# LMS7002M_Power.net
KiCad netlist of a schematic drawn in Altium Designer
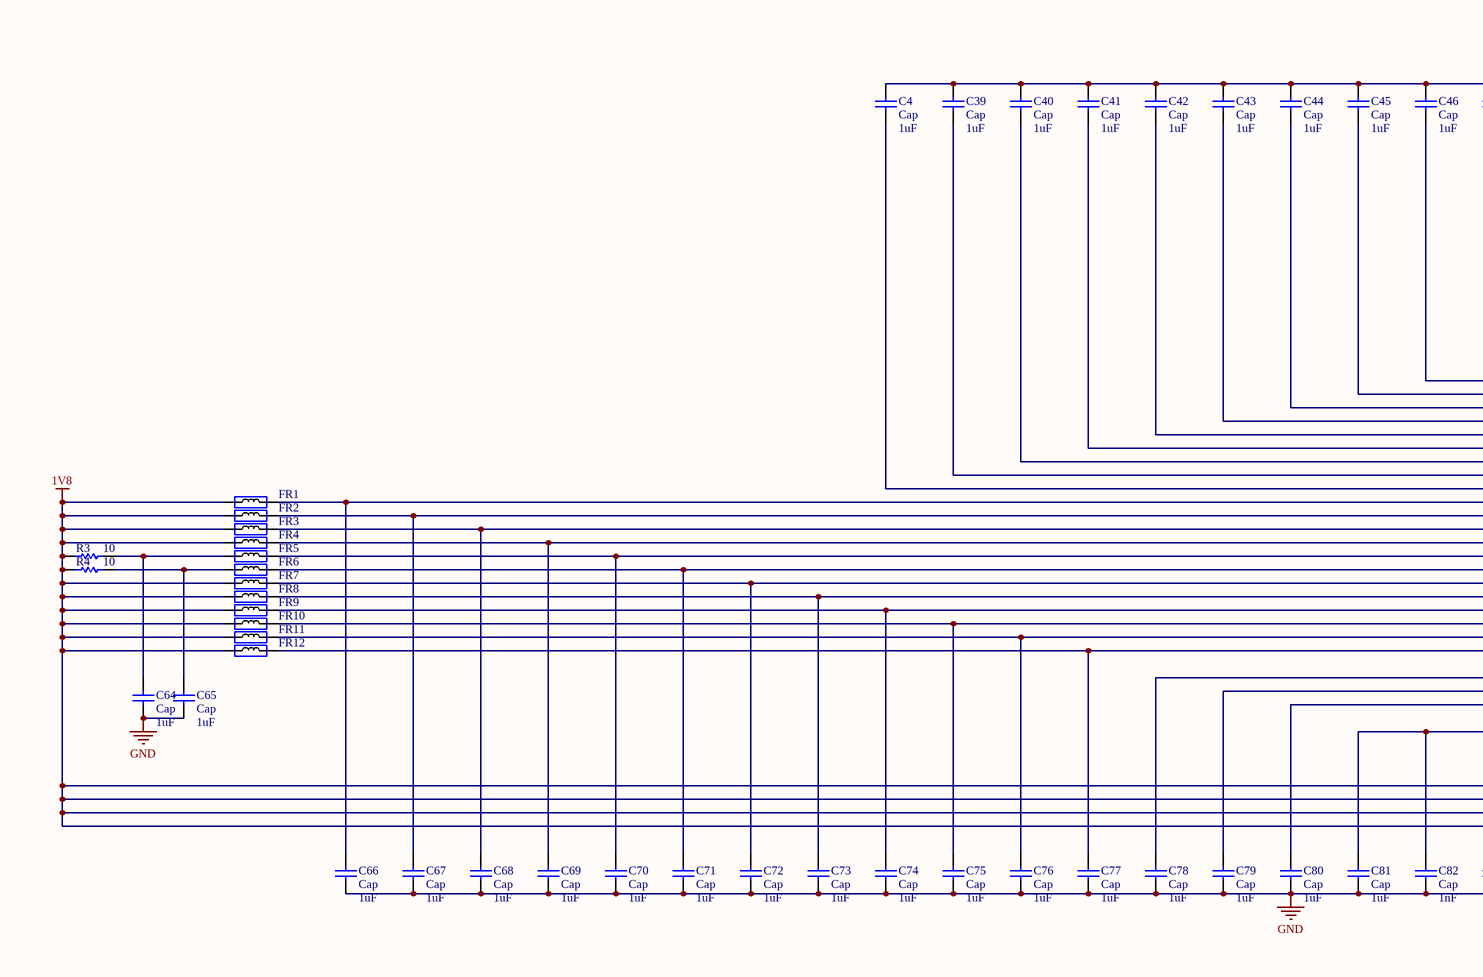
[diagram p0: LMS7002M Power.SchDoc, left]
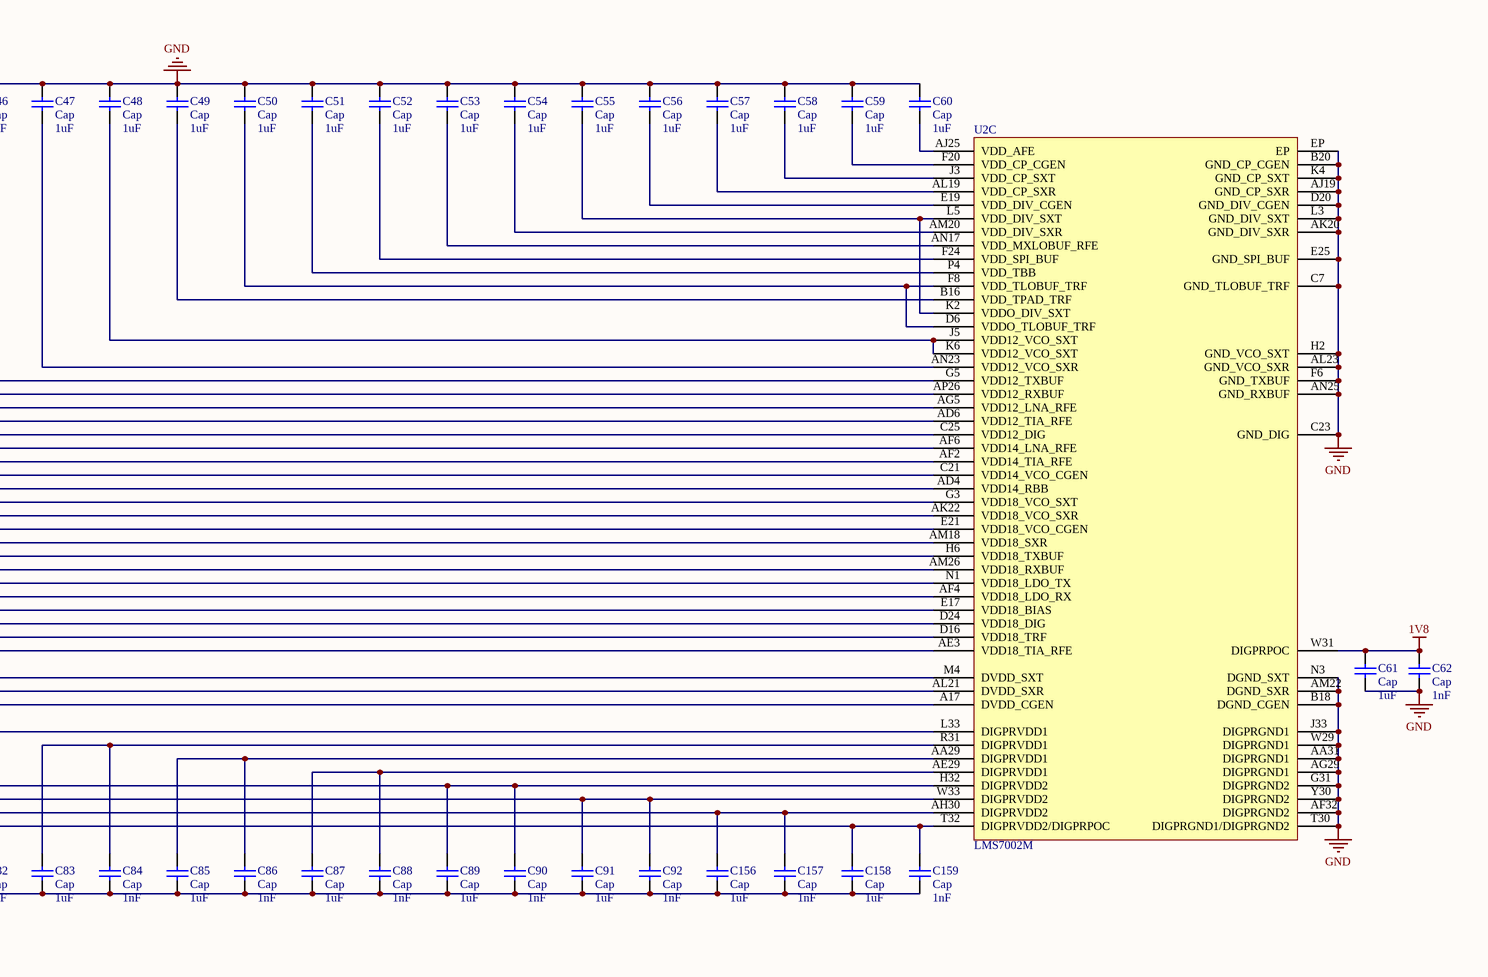
[diagram p1: LMS7002M Power.SchDoc, right]

(export (version "E")
  (design (tool "Eeschema 10.0.6"))
  (components
    (comp (ref "C4")
      (value "Cap")
      (footprint "0603")
      (description "Capacitor")
      (fields (field (name "ALTIUM_VALUE") "1uF") (field (name "PUBLISHER") "Altium Limited"))
      (libsource (lib "Miscellaneous Devices") (part "Cap"))
    )
    (comp (ref "C39")
      (value "Cap")
      (footprint "0603")
      (description "Capacitor")
      (fields (field (name "ALTIUM_VALUE") "1uF") (field (name "PUBLISHER") "Altium Limited"))
      (libsource (lib "Miscellaneous Devices") (part "Cap"))
    )
    (comp (ref "C40")
      (value "Cap")
      (footprint "0603")
      (description "Capacitor")
      (fields (field (name "ALTIUM_VALUE") "1uF") (field (name "PUBLISHER") "Altium Limited"))
      (libsource (lib "Miscellaneous Devices") (part "Cap"))
    )
    (comp (ref "C41")
      (value "Cap")
      (footprint "0603")
      (description "Capacitor")
      (fields (field (name "ALTIUM_VALUE") "1uF") (field (name "PUBLISHER") "Altium Limited"))
      (libsource (lib "Miscellaneous Devices") (part "Cap"))
    )
    (comp (ref "C42")
      (value "Cap")
      (footprint "0603")
      (description "Capacitor")
      (fields (field (name "ALTIUM_VALUE") "1uF") (field (name "PUBLISHER") "Altium Limited"))
      (libsource (lib "Miscellaneous Devices") (part "Cap"))
    )
    (comp (ref "C43")
      (value "Cap")
      (footprint "0603")
      (description "Capacitor")
      (fields (field (name "ALTIUM_VALUE") "1uF") (field (name "PUBLISHER") "Altium Limited"))
      (libsource (lib "Miscellaneous Devices") (part "Cap"))
    )
    (comp (ref "C44")
      (value "Cap")
      (footprint "0603")
      (description "Capacitor")
      (fields (field (name "ALTIUM_VALUE") "1uF") (field (name "PUBLISHER") "Altium Limited"))
      (libsource (lib "Miscellaneous Devices") (part "Cap"))
    )
    (comp (ref "C45")
      (value "Cap")
      (footprint "0603")
      (description "Capacitor")
      (fields (field (name "ALTIUM_VALUE") "1uF") (field (name "PUBLISHER") "Altium Limited"))
      (libsource (lib "Miscellaneous Devices") (part "Cap"))
    )
    (comp (ref "C46")
      (value "Cap")
      (footprint "0603")
      (description "Capacitor")
      (fields (field (name "ALTIUM_VALUE") "1uF") (field (name "PUBLISHER") "Altium Limited"))
      (libsource (lib "Miscellaneous Devices") (part "Cap"))
    )
    (comp (ref "C47")
      (value "Cap")
      (footprint "0603")
      (description "Capacitor")
      (fields (field (name "ALTIUM_VALUE") "1uF") (field (name "PUBLISHER") "Altium Limited"))
      (libsource (lib "Miscellaneous Devices") (part "Cap"))
    )
    (comp (ref "C48")
      (value "Cap")
      (footprint "0603")
      (description "Capacitor")
      (fields (field (name "ALTIUM_VALUE") "1uF") (field (name "PUBLISHER") "Altium Limited"))
      (libsource (lib "Miscellaneous Devices") (part "Cap"))
    )
    (comp (ref "C49")
      (value "Cap")
      (footprint "0603")
      (description "Capacitor")
      (fields (field (name "ALTIUM_VALUE") "1uF") (field (name "PUBLISHER") "Altium Limited"))
      (libsource (lib "Miscellaneous Devices") (part "Cap"))
    )
    (comp (ref "C50")
      (value "Cap")
      (footprint "0603")
      (description "Capacitor")
      (fields (field (name "ALTIUM_VALUE") "1uF") (field (name "PUBLISHER") "Altium Limited"))
      (libsource (lib "Miscellaneous Devices") (part "Cap"))
    )
    (comp (ref "C51")
      (value "Cap")
      (footprint "0603")
      (description "Capacitor")
      (fields (field (name "ALTIUM_VALUE") "1uF") (field (name "PUBLISHER") "Altium Limited"))
      (libsource (lib "Miscellaneous Devices") (part "Cap"))
    )
    (comp (ref "C52")
      (value "Cap")
      (footprint "0603")
      (description "Capacitor")
      (fields (field (name "ALTIUM_VALUE") "1uF") (field (name "PUBLISHER") "Altium Limited"))
      (libsource (lib "Miscellaneous Devices") (part "Cap"))
    )
    (comp (ref "C53")
      (value "Cap")
      (footprint "0603")
      (description "Capacitor")
      (fields (field (name "ALTIUM_VALUE") "1uF") (field (name "PUBLISHER") "Altium Limited"))
      (libsource (lib "Miscellaneous Devices") (part "Cap"))
    )
    (comp (ref "C54")
      (value "Cap")
      (footprint "0603")
      (description "Capacitor")
      (fields (field (name "ALTIUM_VALUE") "1uF") (field (name "PUBLISHER") "Altium Limited"))
      (libsource (lib "Miscellaneous Devices") (part "Cap"))
    )
    (comp (ref "C55")
      (value "Cap")
      (footprint "0603")
      (description "Capacitor")
      (fields (field (name "ALTIUM_VALUE") "1uF") (field (name "PUBLISHER") "Altium Limited"))
      (libsource (lib "Miscellaneous Devices") (part "Cap"))
    )
    (comp (ref "C56")
      (value "Cap")
      (footprint "0603")
      (description "Capacitor")
      (fields (field (name "ALTIUM_VALUE") "1uF") (field (name "PUBLISHER") "Altium Limited"))
      (libsource (lib "Miscellaneous Devices") (part "Cap"))
    )
    (comp (ref "C57")
      (value "Cap")
      (footprint "0603")
      (description "Capacitor")
      (fields (field (name "ALTIUM_VALUE") "1uF") (field (name "PUBLISHER") "Altium Limited"))
      (libsource (lib "Miscellaneous Devices") (part "Cap"))
    )
    (comp (ref "C58")
      (value "Cap")
      (footprint "0603")
      (description "Capacitor")
      (fields (field (name "ALTIUM_VALUE") "1uF") (field (name "PUBLISHER") "Altium Limited"))
      (libsource (lib "Miscellaneous Devices") (part "Cap"))
    )
    (comp (ref "C59")
      (value "Cap")
      (footprint "0603")
      (description "Capacitor")
      (fields (field (name "ALTIUM_VALUE") "1uF") (field (name "PUBLISHER") "Altium Limited"))
      (libsource (lib "Miscellaneous Devices") (part "Cap"))
    )
    (comp (ref "C60")
      (value "Cap")
      (footprint "0603")
      (description "Capacitor")
      (fields (field (name "ALTIUM_VALUE") "1uF") (field (name "PUBLISHER") "Altium Limited"))
      (libsource (lib "Miscellaneous Devices") (part "Cap"))
    )
    (comp (ref "C61")
      (value "Cap")
      (footprint "0603")
      (description "Capacitor")
      (fields (field (name "ALTIUM_VALUE") "1uF") (field (name "PUBLISHER") "Altium Limited"))
      (libsource (lib "Miscellaneous Devices") (part "Cap"))
    )
    (comp (ref "C62")
      (value "Cap")
      (footprint "0603")
      (description "Capacitor")
      (fields (field (name "ALTIUM_VALUE") "1nF") (field (name "PUBLISHER") "Altium Limited"))
      (libsource (lib "Miscellaneous Devices") (part "Cap"))
    )
    (comp (ref "C64")
      (value "Cap")
      (footprint "0603")
      (description "Capacitor")
      (fields (field (name "ALTIUM_VALUE") "1uF") (field (name "PUBLISHER") "Altium Limited"))
      (libsource (lib "Miscellaneous Devices") (part "Cap"))
    )
    (comp (ref "C65")
      (value "Cap")
      (footprint "0603")
      (description "Capacitor")
      (fields (field (name "ALTIUM_VALUE") "1uF") (field (name "PUBLISHER") "Altium Limited"))
      (libsource (lib "Miscellaneous Devices") (part "Cap"))
    )
    (comp (ref "C66")
      (value "Cap")
      (footprint "0603")
      (description "Capacitor")
      (fields (field (name "ALTIUM_VALUE") "1uF") (field (name "PUBLISHER") "Altium Limited"))
      (libsource (lib "Miscellaneous Devices") (part "Cap"))
    )
    (comp (ref "C67")
      (value "Cap")
      (footprint "0603")
      (description "Capacitor")
      (fields (field (name "ALTIUM_VALUE") "1uF") (field (name "PUBLISHER") "Altium Limited"))
      (libsource (lib "Miscellaneous Devices") (part "Cap"))
    )
    (comp (ref "C68")
      (value "Cap")
      (footprint "0603")
      (description "Capacitor")
      (fields (field (name "ALTIUM_VALUE") "1uF") (field (name "PUBLISHER") "Altium Limited"))
      (libsource (lib "Miscellaneous Devices") (part "Cap"))
    )
    (comp (ref "C69")
      (value "Cap")
      (footprint "0603")
      (description "Capacitor")
      (fields (field (name "ALTIUM_VALUE") "1uF") (field (name "PUBLISHER") "Altium Limited"))
      (libsource (lib "Miscellaneous Devices") (part "Cap"))
    )
    (comp (ref "C70")
      (value "Cap")
      (footprint "0603")
      (description "Capacitor")
      (fields (field (name "ALTIUM_VALUE") "1uF") (field (name "PUBLISHER") "Altium Limited"))
      (libsource (lib "Miscellaneous Devices") (part "Cap"))
    )
    (comp (ref "C71")
      (value "Cap")
      (footprint "0603")
      (description "Capacitor")
      (fields (field (name "ALTIUM_VALUE") "1uF") (field (name "PUBLISHER") "Altium Limited"))
      (libsource (lib "Miscellaneous Devices") (part "Cap"))
    )
    (comp (ref "C72")
      (value "Cap")
      (footprint "0603")
      (description "Capacitor")
      (fields (field (name "ALTIUM_VALUE") "1uF") (field (name "PUBLISHER") "Altium Limited"))
      (libsource (lib "Miscellaneous Devices") (part "Cap"))
    )
    (comp (ref "C73")
      (value "Cap")
      (footprint "0603")
      (description "Capacitor")
      (fields (field (name "ALTIUM_VALUE") "1uF") (field (name "PUBLISHER") "Altium Limited"))
      (libsource (lib "Miscellaneous Devices") (part "Cap"))
    )
    (comp (ref "C74")
      (value "Cap")
      (footprint "0603")
      (description "Capacitor")
      (fields (field (name "ALTIUM_VALUE") "1uF") (field (name "PUBLISHER") "Altium Limited"))
      (libsource (lib "Miscellaneous Devices") (part "Cap"))
    )
    (comp (ref "C75")
      (value "Cap")
      (footprint "0603")
      (description "Capacitor")
      (fields (field (name "ALTIUM_VALUE") "1uF") (field (name "PUBLISHER") "Altium Limited"))
      (libsource (lib "Miscellaneous Devices") (part "Cap"))
    )
    (comp (ref "C76")
      (value "Cap")
      (footprint "0603")
      (description "Capacitor")
      (fields (field (name "ALTIUM_VALUE") "1uF") (field (name "PUBLISHER") "Altium Limited"))
      (libsource (lib "Miscellaneous Devices") (part "Cap"))
    )
    (comp (ref "C77")
      (value "Cap")
      (footprint "0603")
      (description "Capacitor")
      (fields (field (name "ALTIUM_VALUE") "1uF") (field (name "PUBLISHER") "Altium Limited"))
      (libsource (lib "Miscellaneous Devices") (part "Cap"))
    )
    (comp (ref "C78")
      (value "Cap")
      (footprint "0603")
      (description "Capacitor")
      (fields (field (name "ALTIUM_VALUE") "1uF") (field (name "PUBLISHER") "Altium Limited"))
      (libsource (lib "Miscellaneous Devices") (part "Cap"))
    )
    (comp (ref "C79")
      (value "Cap")
      (footprint "0603")
      (description "Capacitor")
      (fields (field (name "ALTIUM_VALUE") "1uF") (field (name "PUBLISHER") "Altium Limited"))
      (libsource (lib "Miscellaneous Devices") (part "Cap"))
    )
    (comp (ref "C80")
      (value "Cap")
      (footprint "0603")
      (description "Capacitor")
      (fields (field (name "ALTIUM_VALUE") "1uF") (field (name "PUBLISHER") "Altium Limited"))
      (libsource (lib "Miscellaneous Devices") (part "Cap"))
    )
    (comp (ref "C81")
      (value "Cap")
      (footprint "0603")
      (description "Capacitor")
      (fields (field (name "ALTIUM_VALUE") "1uF") (field (name "PUBLISHER") "Altium Limited"))
      (libsource (lib "Miscellaneous Devices") (part "Cap"))
    )
    (comp (ref "C82")
      (value "Cap")
      (footprint "0603")
      (description "Capacitor")
      (fields (field (name "ALTIUM_VALUE") "1nF") (field (name "PUBLISHER") "Altium Limited"))
      (libsource (lib "Miscellaneous Devices") (part "Cap"))
    )
    (comp (ref "C83")
      (value "Cap")
      (footprint "0603")
      (description "Capacitor")
      (fields (field (name "ALTIUM_VALUE") "1uF") (field (name "PUBLISHER") "Altium Limited"))
      (libsource (lib "Miscellaneous Devices") (part "Cap"))
    )
    (comp (ref "C84")
      (value "Cap")
      (footprint "0603")
      (description "Capacitor")
      (fields (field (name "ALTIUM_VALUE") "1nF") (field (name "PUBLISHER") "Altium Limited"))
      (libsource (lib "Miscellaneous Devices") (part "Cap"))
    )
    (comp (ref "C85")
      (value "Cap")
      (footprint "0603")
      (description "Capacitor")
      (fields (field (name "ALTIUM_VALUE") "1uF") (field (name "PUBLISHER") "Altium Limited"))
      (libsource (lib "Miscellaneous Devices") (part "Cap"))
    )
    (comp (ref "C86")
      (value "Cap")
      (footprint "0603")
      (description "Capacitor")
      (fields (field (name "ALTIUM_VALUE") "1nF") (field (name "PUBLISHER") "Altium Limited"))
      (libsource (lib "Miscellaneous Devices") (part "Cap"))
    )
    (comp (ref "C87")
      (value "Cap")
      (footprint "0603")
      (description "Capacitor")
      (fields (field (name "ALTIUM_VALUE") "1uF") (field (name "PUBLISHER") "Altium Limited"))
      (libsource (lib "Miscellaneous Devices") (part "Cap"))
    )
    (comp (ref "C88")
      (value "Cap")
      (footprint "0603")
      (description "Capacitor")
      (fields (field (name "ALTIUM_VALUE") "1nF") (field (name "PUBLISHER") "Altium Limited"))
      (libsource (lib "Miscellaneous Devices") (part "Cap"))
    )
    (comp (ref "C89")
      (value "Cap")
      (footprint "0603")
      (description "Capacitor")
      (fields (field (name "ALTIUM_VALUE") "1uF") (field (name "PUBLISHER") "Altium Limited"))
      (libsource (lib "Miscellaneous Devices") (part "Cap"))
    )
    (comp (ref "C90")
      (value "Cap")
      (footprint "0603")
      (description "Capacitor")
      (fields (field (name "ALTIUM_VALUE") "1nF") (field (name "PUBLISHER") "Altium Limited"))
      (libsource (lib "Miscellaneous Devices") (part "Cap"))
    )
    (comp (ref "C91")
      (value "Cap")
      (footprint "0603")
      (description "Capacitor")
      (fields (field (name "ALTIUM_VALUE") "1uF") (field (name "PUBLISHER") "Altium Limited"))
      (libsource (lib "Miscellaneous Devices") (part "Cap"))
    )
    (comp (ref "C92")
      (value "Cap")
      (footprint "0603")
      (description "Capacitor")
      (fields (field (name "ALTIUM_VALUE") "1nF") (field (name "PUBLISHER") "Altium Limited"))
      (libsource (lib "Miscellaneous Devices") (part "Cap"))
    )
    (comp (ref "C156")
      (value "Cap")
      (footprint "0603")
      (description "Capacitor")
      (fields (field (name "ALTIUM_VALUE") "1uF") (field (name "PUBLISHER") "Altium Limited"))
      (libsource (lib "Miscellaneous Devices") (part "Cap"))
    )
    (comp (ref "C157")
      (value "Cap")
      (footprint "0603")
      (description "Capacitor")
      (fields (field (name "ALTIUM_VALUE") "1nF") (field (name "PUBLISHER") "Altium Limited"))
      (libsource (lib "Miscellaneous Devices") (part "Cap"))
    )
    (comp (ref "C158")
      (value "Cap")
      (footprint "0603")
      (description "Capacitor")
      (fields (field (name "ALTIUM_VALUE") "1uF") (field (name "PUBLISHER") "Altium Limited"))
      (libsource (lib "Miscellaneous Devices") (part "Cap"))
    )
    (comp (ref "C159")
      (value "Cap")
      (footprint "0603")
      (description "Capacitor")
      (fields (field (name "ALTIUM_VALUE") "1nF") (field (name "PUBLISHER") "Altium Limited"))
      (libsource (lib "Miscellaneous Devices") (part "Cap"))
    )
    (comp (ref "FR1")
      (value "600R, 0.27A")
      (footprint "0603")
      (fields (field (name "MANUFACTURER") "Taiyo Yuden"))
      (libsource (lib "LimeMicroAltiumLib_schLib") (part "Ferrite"))
    )
    (comp (ref "FR2")
      (value "600R, 0.27A")
      (footprint "0603")
      (fields (field (name "MANUFACTURER") "Taiyo Yuden"))
      (libsource (lib "LimeMicroAltiumLib_schLib") (part "Ferrite"))
    )
    (comp (ref "FR3")
      (value "600R, 0.27A")
      (footprint "0603")
      (fields (field (name "MANUFACTURER") "Taiyo Yuden"))
      (libsource (lib "LimeMicroAltiumLib_schLib") (part "Ferrite"))
    )
    (comp (ref "FR4")
      (value "600R, 0.27A")
      (footprint "0603")
      (fields (field (name "MANUFACTURER") "Taiyo Yuden"))
      (libsource (lib "LimeMicroAltiumLib_schLib") (part "Ferrite"))
    )
    (comp (ref "FR5")
      (value "600R, 0.27A")
      (footprint "0603")
      (fields (field (name "MANUFACTURER") "Taiyo Yuden"))
      (libsource (lib "LimeMicroAltiumLib_schLib") (part "Ferrite"))
    )
    (comp (ref "FR6")
      (value "600R, 0.27A")
      (footprint "0603")
      (fields (field (name "MANUFACTURER") "Taiyo Yuden"))
      (libsource (lib "LimeMicroAltiumLib_schLib") (part "Ferrite"))
    )
    (comp (ref "FR7")
      (value "600R, 0.27A")
      (footprint "0603")
      (fields (field (name "MANUFACTURER") "Taiyo Yuden"))
      (libsource (lib "LimeMicroAltiumLib_schLib") (part "Ferrite"))
    )
    (comp (ref "FR8")
      (value "600R, 0.27A")
      (footprint "0603")
      (fields (field (name "MANUFACTURER") "Taiyo Yuden"))
      (libsource (lib "LimeMicroAltiumLib_schLib") (part "Ferrite"))
    )
    (comp (ref "FR9")
      (value "600R, 0.27A")
      (footprint "0603")
      (fields (field (name "MANUFACTURER") "Taiyo Yuden"))
      (libsource (lib "LimeMicroAltiumLib_schLib") (part "Ferrite"))
    )
    (comp (ref "FR10")
      (value "600R, 0.27A")
      (footprint "0603")
      (fields (field (name "MANUFACTURER") "Taiyo Yuden"))
      (libsource (lib "LimeMicroAltiumLib_schLib") (part "Ferrite"))
    )
    (comp (ref "FR11")
      (value "600R, 0.27A")
      (footprint "0603")
      (fields (field (name "MANUFACTURER") "Taiyo Yuden"))
      (libsource (lib "LimeMicroAltiumLib_schLib") (part "Ferrite"))
    )
    (comp (ref "FR12")
      (value "600R, 0.27A")
      (footprint "0603")
      (fields (field (name "MANUFACTURER") "Taiyo Yuden"))
      (libsource (lib "LimeMicroAltiumLib_schLib") (part "Ferrite"))
    )
    (comp (ref "R3")
      (value "10")
      (footprint "0402-A")
      (description "Resistor")
      (fields (field (name "Comment") "Res1") (field (name "PUBLISHER") "Altium Limited"))
      (libsource (lib "Miscellaneous Devices") (part "Res1"))
    )
    (comp (ref "R4")
      (value "10")
      (footprint "0402-A")
      (description "Resistor")
      (fields (field (name "Comment") "Res1") (field (name "PUBLISHER") "Altium Limited"))
      (libsource (lib "Miscellaneous Devices") (part "Res1"))
    )
    (comp (ref "U2")
      (value "LMS7002M")
      (footprint "LM-QFN-261_V")
      (fields (field (name "MANUFACTURER") "LimeMicrosystemsLtd"))
      (libsource (lib "Altium Content Vault") (part "LM-LMS7002M-QFN-261"))
    )
  )
  (nets
    (net (code "1") (name "1V8") (class "Default")
      (node (ref "C156") (pin "2") (pinfunction "2_2") (pintype "passive"))
      (node (ref "C157") (pin "2") (pinfunction "2_2") (pintype "passive"))
      (node (ref "C158") (pin "2") (pinfunction "2_2") (pintype "passive"))
      (node (ref "C159") (pin "2") (pinfunction "2_2") (pintype "passive"))
      (node (ref "C61") (pin "2") (pinfunction "2_2") (pintype "passive"))
      (node (ref "C62") (pin "2") (pinfunction "2_2") (pintype "passive"))
      (node (ref "C89") (pin "2") (pinfunction "2_2") (pintype "passive"))
      (node (ref "C90") (pin "2") (pinfunction "2_2") (pintype "passive"))
      (node (ref "C91") (pin "2") (pinfunction "2_2") (pintype "passive"))
      (node (ref "C92") (pin "2") (pinfunction "2_2") (pintype "passive"))
      (node (ref "FR1") (pin "1") (pinfunction "1_1") (pintype "passive"))
      (node (ref "FR10") (pin "1") (pinfunction "1_1") (pintype "passive"))
      (node (ref "FR11") (pin "1") (pinfunction "1_1") (pintype "passive"))
      (node (ref "FR12") (pin "1") (pinfunction "1_1") (pintype "passive"))
      (node (ref "FR2") (pin "1") (pinfunction "1_1") (pintype "passive"))
      (node (ref "FR3") (pin "1") (pinfunction "1_1") (pintype "passive"))
      (node (ref "FR4") (pin "1") (pinfunction "1_1") (pintype "passive"))
      (node (ref "FR7") (pin "1") (pinfunction "1_1") (pintype "passive"))
      (node (ref "FR8") (pin "1") (pinfunction "1_1") (pintype "passive"))
      (node (ref "FR9") (pin "1") (pinfunction "1_1") (pintype "passive"))
      (node (ref "R3") (pin "1") (pinfunction "1_1") (pintype "passive"))
      (node (ref "R4") (pin "1") (pinfunction "1_1") (pintype "passive"))
      (node (ref "U2") (pin "AH30") (pinfunction "DIGPRVDD2_AH30") (pintype "power_in"))
      (node (ref "U2") (pin "H32") (pinfunction "DIGPRVDD2_H32") (pintype "power_in"))
      (node (ref "U2") (pin "T32") (pinfunction "DIGPRVDD2/DIGPRPOC_T32") (pintype "power_in"))
      (node (ref "U2") (pin "W31") (pinfunction "DIGPRPOC_W31") (pintype "passive"))
      (node (ref "U2") (pin "W33") (pinfunction "DIGPRVDD2_W33") (pintype "power_in"))
    )
    (net (code "2") (name "GND") (class "Default")
      (node (ref "C156") (pin "1") (pinfunction "1_1") (pintype "passive"))
      (node (ref "C157") (pin "1") (pinfunction "1_1") (pintype "passive"))
      (node (ref "C158") (pin "1") (pinfunction "1_1") (pintype "passive"))
      (node (ref "C159") (pin "1") (pinfunction "1_1") (pintype "passive"))
      (node (ref "C39") (pin "2") (pinfunction "2_2") (pintype "passive"))
      (node (ref "C4") (pin "2") (pinfunction "2_2") (pintype "passive"))
      (node (ref "C40") (pin "2") (pinfunction "2_2") (pintype "passive"))
      (node (ref "C41") (pin "2") (pinfunction "2_2") (pintype "passive"))
      (node (ref "C42") (pin "2") (pinfunction "2_2") (pintype "passive"))
      (node (ref "C43") (pin "2") (pinfunction "2_2") (pintype "passive"))
      (node (ref "C44") (pin "2") (pinfunction "2_2") (pintype "passive"))
      (node (ref "C45") (pin "2") (pinfunction "2_2") (pintype "passive"))
      (node (ref "C46") (pin "2") (pinfunction "2_2") (pintype "passive"))
      (node (ref "C47") (pin "2") (pinfunction "2_2") (pintype "passive"))
      (node (ref "C48") (pin "2") (pinfunction "2_2") (pintype "passive"))
      (node (ref "C49") (pin "2") (pinfunction "2_2") (pintype "passive"))
      (node (ref "C50") (pin "2") (pinfunction "2_2") (pintype "passive"))
      (node (ref "C51") (pin "2") (pinfunction "2_2") (pintype "passive"))
      (node (ref "C52") (pin "2") (pinfunction "2_2") (pintype "passive"))
      (node (ref "C53") (pin "2") (pinfunction "2_2") (pintype "passive"))
      (node (ref "C54") (pin "2") (pinfunction "2_2") (pintype "passive"))
      (node (ref "C55") (pin "2") (pinfunction "2_2") (pintype "passive"))
      (node (ref "C56") (pin "2") (pinfunction "2_2") (pintype "passive"))
      (node (ref "C57") (pin "2") (pinfunction "2_2") (pintype "passive"))
      (node (ref "C58") (pin "2") (pinfunction "2_2") (pintype "passive"))
      (node (ref "C59") (pin "2") (pinfunction "2_2") (pintype "passive"))
      (node (ref "C60") (pin "2") (pinfunction "2_2") (pintype "passive"))
      (node (ref "C61") (pin "1") (pinfunction "1_1") (pintype "passive"))
      (node (ref "C62") (pin "1") (pinfunction "1_1") (pintype "passive"))
      (node (ref "C64") (pin "1") (pinfunction "1_1") (pintype "passive"))
      (node (ref "C65") (pin "1") (pinfunction "1_1") (pintype "passive"))
      (node (ref "C66") (pin "1") (pinfunction "1_1") (pintype "passive"))
      (node (ref "C67") (pin "1") (pinfunction "1_1") (pintype "passive"))
      (node (ref "C68") (pin "1") (pinfunction "1_1") (pintype "passive"))
      (node (ref "C69") (pin "1") (pinfunction "1_1") (pintype "passive"))
      (node (ref "C70") (pin "1") (pinfunction "1_1") (pintype "passive"))
      (node (ref "C71") (pin "1") (pinfunction "1_1") (pintype "passive"))
      (node (ref "C72") (pin "1") (pinfunction "1_1") (pintype "passive"))
      (node (ref "C73") (pin "1") (pinfunction "1_1") (pintype "passive"))
      (node (ref "C74") (pin "1") (pinfunction "1_1") (pintype "passive"))
      (node (ref "C75") (pin "1") (pinfunction "1_1") (pintype "passive"))
      (node (ref "C76") (pin "1") (pinfunction "1_1") (pintype "passive"))
      (node (ref "C77") (pin "1") (pinfunction "1_1") (pintype "passive"))
      (node (ref "C78") (pin "1") (pinfunction "1_1") (pintype "passive"))
      (node (ref "C79") (pin "1") (pinfunction "1_1") (pintype "passive"))
      (node (ref "C80") (pin "1") (pinfunction "1_1") (pintype "passive"))
      (node (ref "C81") (pin "1") (pinfunction "1_1") (pintype "passive"))
      (node (ref "C82") (pin "1") (pinfunction "1_1") (pintype "passive"))
      (node (ref "C83") (pin "1") (pinfunction "1_1") (pintype "passive"))
      (node (ref "C84") (pin "1") (pinfunction "1_1") (pintype "passive"))
      (node (ref "C85") (pin "1") (pinfunction "1_1") (pintype "passive"))
      (node (ref "C86") (pin "1") (pinfunction "1_1") (pintype "passive"))
      (node (ref "C87") (pin "1") (pinfunction "1_1") (pintype "passive"))
      (node (ref "C88") (pin "1") (pinfunction "1_1") (pintype "passive"))
      (node (ref "C89") (pin "1") (pinfunction "1_1") (pintype "passive"))
      (node (ref "C90") (pin "1") (pinfunction "1_1") (pintype "passive"))
      (node (ref "C91") (pin "1") (pinfunction "1_1") (pintype "passive"))
      (node (ref "C92") (pin "1") (pinfunction "1_1") (pintype "passive"))
      (node (ref "U2") (pin "AA31") (pinfunction "DIGPRGND1_AA31") (pintype "power_in"))
      (node (ref "U2") (pin "AF32") (pinfunction "DIGPRGND2_AF32") (pintype "power_in"))
      (node (ref "U2") (pin "AG29") (pinfunction "DIGPRGND1_AG29") (pintype "power_in"))
      (node (ref "U2") (pin "AJ19") (pinfunction "GND_CP_SXR_AJ19") (pintype "power_in"))
      (node (ref "U2") (pin "AK20") (pinfunction "GND_DIV_SXR_AK20") (pintype "power_in"))
      (node (ref "U2") (pin "AL23") (pinfunction "GND_VCO_SXR_AL23") (pintype "power_in"))
      (node (ref "U2") (pin "AM22") (pinfunction "DGND_SXR_AM22") (pintype "power_in"))
      (node (ref "U2") (pin "AN25") (pinfunction "GND_RXBUF_AN25") (pintype "power_in"))
      (node (ref "U2") (pin "B18") (pinfunction "DGND_CGEN_B18") (pintype "power_in"))
      (node (ref "U2") (pin "B20") (pinfunction "GND_CP_CGEN_B20") (pintype "power_in"))
      (node (ref "U2") (pin "C23") (pinfunction "GND_DIG_C23") (pintype "power_in"))
      (node (ref "U2") (pin "C7") (pinfunction "GND_TLOBUF_TRF_C7") (pintype "power_in"))
      (node (ref "U2") (pin "D20") (pinfunction "GND_DIV_CGEN_D20") (pintype "power_in"))
      (node (ref "U2") (pin "E25") (pinfunction "GND_SPI_BUF_E25") (pintype "power_in"))
      (node (ref "U2") (pin "EP") (pinfunction "EP_EP") (pintype "passive"))
      (node (ref "U2") (pin "F6") (pinfunction "GND_TXBUF_F6") (pintype "power_in"))
      (node (ref "U2") (pin "G31") (pinfunction "DIGPRGND2_G31") (pintype "power_in"))
      (node (ref "U2") (pin "H2") (pinfunction "GND_VCO_SXT_H2") (pintype "power_in"))
      (node (ref "U2") (pin "J33") (pinfunction "DIGPRGND1_J33") (pintype "power_in"))
      (node (ref "U2") (pin "K4") (pinfunction "GND_CP_SXT_K4") (pintype "power_in"))
      (node (ref "U2") (pin "L3") (pinfunction "GND_DIV_SXT_L3") (pintype "power_in"))
      (node (ref "U2") (pin "N3") (pinfunction "DGND_SXT_N3") (pintype "power_in"))
      (node (ref "U2") (pin "T30") (pinfunction "DIGPRGND1/DIGPRGND2_T30") (pintype "power_in"))
      (node (ref "U2") (pin "W29") (pinfunction "DIGPRGND1_W29") (pintype "power_in"))
      (node (ref "U2") (pin "Y30") (pinfunction "DIGPRGND2_Y30") (pintype "power_in"))
    )
    (net (code "3") (name "Net-(C48-Pad1)") (class "Default")
      (node (ref "C48") (pin "1") (pinfunction "1_1") (pintype "passive"))
      (node (ref "U2") (pin "J5") (pinfunction "VDD12_VCO_SXT_J5") (pintype "power_in"))
      (node (ref "U2") (pin "K6") (pinfunction "VDD12_VCO_SXT_K6") (pintype "power_in"))
    )
    (net (code "4") (name "Net-(C64-Pad2)") (class "Default")
      (node (ref "C64") (pin "2") (pinfunction "2_2") (pintype "passive"))
      (node (ref "FR5") (pin "1") (pinfunction "1_1") (pintype "passive"))
      (node (ref "R3") (pin "2") (pinfunction "2_2") (pintype "passive"))
    )
    (net (code "5") (name "Net-(C65-Pad2)") (class "Default")
      (node (ref "C65") (pin "2") (pinfunction "2_2") (pintype "passive"))
      (node (ref "FR6") (pin "1") (pinfunction "1_1") (pintype "passive"))
      (node (ref "R4") (pin "2") (pinfunction "2_2") (pintype "passive"))
    )
    (net (code "6") (name "Net-(C81-Pad2)") (class "Default")
      (node (ref "C81") (pin "2") (pinfunction "2_2") (pintype "passive"))
      (node (ref "C82") (pin "2") (pinfunction "2_2") (pintype "passive"))
      (node (ref "U2") (pin "L33") (pinfunction "DIGPRVDD1_L33") (pintype "power_in"))
    )
    (net (code "7") (name "Net-(C83-Pad2)") (class "Default")
      (node (ref "C83") (pin "2") (pinfunction "2_2") (pintype "passive"))
      (node (ref "C84") (pin "2") (pinfunction "2_2") (pintype "passive"))
      (node (ref "U2") (pin "R31") (pinfunction "DIGPRVDD1_R31") (pintype "power_in"))
    )
    (net (code "8") (name "Net-(C85-Pad2)") (class "Default")
      (node (ref "C85") (pin "2") (pinfunction "2_2") (pintype "passive"))
      (node (ref "C86") (pin "2") (pinfunction "2_2") (pintype "passive"))
      (node (ref "U2") (pin "AA29") (pinfunction "DIGPRVDD1_AA29") (pintype "power_in"))
    )
    (net (code "9") (name "Net-(C87-Pad2)") (class "Default")
      (node (ref "C87") (pin "2") (pinfunction "2_2") (pintype "passive"))
      (node (ref "C88") (pin "2") (pinfunction "2_2") (pintype "passive"))
      (node (ref "U2") (pin "AE29") (pinfunction "DIGPRVDD1_AE29") (pintype "power_in"))
    )
    (net (code "10") (name "Net-(U2C-DVDD_CGEN)") (class "Default")
      (node (ref "C80") (pin "2") (pinfunction "2_2") (pintype "passive"))
      (node (ref "U2") (pin "A17") (pinfunction "DVDD_CGEN_A17") (pintype "power_in"))
    )
    (net (code "11") (name "Net-(U2C-DVDD_SXR)") (class "Default")
      (node (ref "C79") (pin "2") (pinfunction "2_2") (pintype "passive"))
      (node (ref "U2") (pin "AL21") (pinfunction "DVDD_SXR_AL21") (pintype "power_in"))
    )
    (net (code "12") (name "Net-(U2C-DVDD_SXT)") (class "Default")
      (node (ref "C78") (pin "2") (pinfunction "2_2") (pintype "passive"))
      (node (ref "U2") (pin "M4") (pinfunction "DVDD_SXT_M4") (pintype "power_in"))
    )
    (net (code "13") (name "Net-(U2C-VDD12_DIG)") (class "Default")
      (node (ref "C42") (pin "1") (pinfunction "1_1") (pintype "passive"))
      (node (ref "U2") (pin "C25") (pinfunction "VDD12_DIG_C25") (pintype "power_in"))
    )
    (net (code "14") (name "Net-(U2C-VDD12_LNA_RFE)") (class "Default")
      (node (ref "C44") (pin "1") (pinfunction "1_1") (pintype "passive"))
      (node (ref "U2") (pin "AG5") (pinfunction "VDD12_LNA_RFE_AG5") (pintype "power_in"))
    )
    (net (code "15") (name "Net-(U2C-VDD12_RXBUF)") (class "Default")
      (node (ref "C45") (pin "1") (pinfunction "1_1") (pintype "passive"))
      (node (ref "U2") (pin "AP26") (pinfunction "VDD12_RXBUF_AP26") (pintype "power_in"))
    )
    (net (code "16") (name "Net-(U2C-VDD12_TIA_RFE)") (class "Default")
      (node (ref "C43") (pin "1") (pinfunction "1_1") (pintype "passive"))
      (node (ref "U2") (pin "AD6") (pinfunction "VDD12_TIA_RFE_AD6") (pintype "power_in"))
    )
    (net (code "17") (name "Net-(U2C-VDD12_TXBUF)") (class "Default")
      (node (ref "C46") (pin "1") (pinfunction "1_1") (pintype "passive"))
      (node (ref "U2") (pin "G5") (pinfunction "VDD12_TXBUF_G5") (pintype "power_in"))
    )
    (net (code "18") (name "Net-(U2C-VDD12_VCO_SXR)") (class "Default")
      (node (ref "C47") (pin "1") (pinfunction "1_1") (pintype "passive"))
      (node (ref "U2") (pin "AN23") (pinfunction "VDD12_VCO_SXR_AN23") (pintype "power_in"))
    )
    (net (code "19") (name "Net-(U2C-VDD14_LNA_RFE)") (class "Default")
      (node (ref "C41") (pin "1") (pinfunction "1_1") (pintype "passive"))
      (node (ref "U2") (pin "AF6") (pinfunction "VDD14_LNA_RFE_AF6") (pintype "power_in"))
    )
    (net (code "20") (name "Net-(U2C-VDD14_RBB)") (class "Default")
      (node (ref "C4") (pin "1") (pinfunction "1_1") (pintype "passive"))
      (node (ref "U2") (pin "AD4") (pinfunction "VDD14_RBB_AD4") (pintype "power_in"))
    )
    (net (code "21") (name "Net-(U2C-VDD14_TIA_RFE)") (class "Default")
      (node (ref "C40") (pin "1") (pinfunction "1_1") (pintype "passive"))
      (node (ref "U2") (pin "AF2") (pinfunction "VDD14_TIA_RFE_AF2") (pintype "power_in"))
    )
    (net (code "22") (name "Net-(U2C-VDD14_VCO_CGEN)") (class "Default")
      (node (ref "C39") (pin "1") (pinfunction "1_1") (pintype "passive"))
      (node (ref "U2") (pin "C21") (pinfunction "VDD14_VCO_CGEN_C21") (pintype "power_in"))
    )
    (net (code "23") (name "Net-(U2C-VDD18_BIAS)") (class "Default")
      (node (ref "C74") (pin "2") (pinfunction "2_2") (pintype "passive"))
      (node (ref "FR9") (pin "2") (pinfunction "2_2") (pintype "passive"))
      (node (ref "U2") (pin "E17") (pinfunction "VDD18_BIAS_E17") (pintype "power_in"))
    )
    (net (code "24") (name "Net-(U2C-VDD18_DIG)") (class "Default")
      (node (ref "C75") (pin "2") (pinfunction "2_2") (pintype "passive"))
      (node (ref "FR10") (pin "2") (pinfunction "2_2") (pintype "passive"))
      (node (ref "U2") (pin "D24") (pinfunction "VDD18_DIG_D24") (pintype "power_in"))
    )
    (net (code "25") (name "Net-(U2C-VDD18_LDO_RX)") (class "Default")
      (node (ref "C73") (pin "2") (pinfunction "2_2") (pintype "passive"))
      (node (ref "FR8") (pin "2") (pinfunction "2_2") (pintype "passive"))
      (node (ref "U2") (pin "AF4") (pinfunction "VDD18_LDO_RX_AF4") (pintype "power_in"))
    )
    (net (code "26") (name "Net-(U2C-VDD18_LDO_TX)") (class "Default")
      (node (ref "C72") (pin "2") (pinfunction "2_2") (pintype "passive"))
      (node (ref "FR7") (pin "2") (pinfunction "2_2") (pintype "passive"))
      (node (ref "U2") (pin "N1") (pinfunction "VDD18_LDO_TX_N1") (pintype "power_in"))
    )
    (net (code "27") (name "Net-(U2C-VDD18_RXBUF)") (class "Default")
      (node (ref "C71") (pin "2") (pinfunction "2_2") (pintype "passive"))
      (node (ref "FR6") (pin "2") (pinfunction "2_2") (pintype "passive"))
      (node (ref "U2") (pin "AM26") (pinfunction "VDD18_RXBUF_AM26") (pintype "power_in"))
    )
    (net (code "28") (name "Net-(U2C-VDD18_SXR)") (class "Default")
      (node (ref "C69") (pin "2") (pinfunction "2_2") (pintype "passive"))
      (node (ref "FR4") (pin "2") (pinfunction "2_2") (pintype "passive"))
      (node (ref "U2") (pin "AM18") (pinfunction "VDD18_SXR_AM18") (pintype "power_in"))
    )
    (net (code "29") (name "Net-(U2C-VDD18_TIA_RFE)") (class "Default")
      (node (ref "C77") (pin "2") (pinfunction "2_2") (pintype "passive"))
      (node (ref "FR12") (pin "2") (pinfunction "2_2") (pintype "passive"))
      (node (ref "U2") (pin "AE3") (pinfunction "VDD18_TIA_RFE_AE3") (pintype "power_in"))
    )
    (net (code "30") (name "Net-(U2C-VDD18_TRF)") (class "Default")
      (node (ref "C76") (pin "2") (pinfunction "2_2") (pintype "passive"))
      (node (ref "FR11") (pin "2") (pinfunction "2_2") (pintype "passive"))
      (node (ref "U2") (pin "D16") (pinfunction "VDD18_TRF_D16") (pintype "power_in"))
    )
    (net (code "31") (name "Net-(U2C-VDD18_TXBUF)") (class "Default")
      (node (ref "C70") (pin "2") (pinfunction "2_2") (pintype "passive"))
      (node (ref "FR5") (pin "2") (pinfunction "2_2") (pintype "passive"))
      (node (ref "U2") (pin "H6") (pinfunction "VDD18_TXBUF_H6") (pintype "power_in"))
    )
    (net (code "32") (name "Net-(U2C-VDD18_VCO_CGEN)") (class "Default")
      (node (ref "C68") (pin "2") (pinfunction "2_2") (pintype "passive"))
      (node (ref "FR3") (pin "2") (pinfunction "2_2") (pintype "passive"))
      (node (ref "U2") (pin "E21") (pinfunction "VDD18_VCO_CGEN_E21") (pintype "power_in"))
    )
    (net (code "33") (name "Net-(U2C-VDD18_VCO_SXR)") (class "Default")
      (node (ref "C67") (pin "2") (pinfunction "2_2") (pintype "passive"))
      (node (ref "FR2") (pin "2") (pinfunction "2_2") (pintype "passive"))
      (node (ref "U2") (pin "AK22") (pinfunction "VDD18_VCO_SXR_AK22") (pintype "power_in"))
    )
    (net (code "34") (name "Net-(U2C-VDD18_VCO_SXT)") (class "Default")
      (node (ref "C66") (pin "2") (pinfunction "2_2") (pintype "passive"))
      (node (ref "FR1") (pin "2") (pinfunction "2_2") (pintype "passive"))
      (node (ref "U2") (pin "G3") (pinfunction "VDD18_VCO_SXT_G3") (pintype "power_in"))
    )
    (net (code "35") (name "Net-(U2C-VDDO_DIV_SXT)") (class "Default")
      (node (ref "C55") (pin "1") (pinfunction "1_1") (pintype "passive"))
      (node (ref "U2") (pin "K2") (pinfunction "VDDO_DIV_SXT_K2") (pintype "power_in"))
      (node (ref "U2") (pin "L5") (pinfunction "VDD_DIV_SXT_L5") (pintype "power_in"))
    )
    (net (code "36") (name "Net-(U2C-VDDO_TLOBUF_TRF)") (class "Default")
      (node (ref "C50") (pin "1") (pinfunction "1_1") (pintype "passive"))
      (node (ref "U2") (pin "D6") (pinfunction "VDDO_TLOBUF_TRF_D6") (pintype "power_in"))
      (node (ref "U2") (pin "F8") (pinfunction "VDD_TLOBUF_TRF_F8") (pintype "power_in"))
    )
    (net (code "37") (name "Net-(U2C-VDD_AFE)") (class "Default")
      (node (ref "C60") (pin "1") (pinfunction "1_1") (pintype "passive"))
      (node (ref "U2") (pin "AJ25") (pinfunction "VDD_AFE_AJ25") (pintype "power_in"))
    )
    (net (code "38") (name "Net-(U2C-VDD_CP_CGEN)") (class "Default")
      (node (ref "C59") (pin "1") (pinfunction "1_1") (pintype "passive"))
      (node (ref "U2") (pin "F20") (pinfunction "VDD_CP_CGEN_F20") (pintype "power_in"))
    )
    (net (code "39") (name "Net-(U2C-VDD_CP_SXR)") (class "Default")
      (node (ref "C57") (pin "1") (pinfunction "1_1") (pintype "passive"))
      (node (ref "U2") (pin "AL19") (pinfunction "VDD_CP_SXR_AL19") (pintype "power_in"))
    )
    (net (code "40") (name "Net-(U2C-VDD_CP_SXT)") (class "Default")
      (node (ref "C58") (pin "1") (pinfunction "1_1") (pintype "passive"))
      (node (ref "U2") (pin "J3") (pinfunction "VDD_CP_SXT_J3") (pintype "power_in"))
    )
    (net (code "41") (name "Net-(U2C-VDD_DIV_CGEN)") (class "Default")
      (node (ref "C56") (pin "1") (pinfunction "1_1") (pintype "passive"))
      (node (ref "U2") (pin "E19") (pinfunction "VDD_DIV_CGEN_E19") (pintype "power_in"))
    )
    (net (code "42") (name "Net-(U2C-VDD_DIV_SXR)") (class "Default")
      (node (ref "C54") (pin "1") (pinfunction "1_1") (pintype "passive"))
      (node (ref "U2") (pin "AM20") (pinfunction "VDD_DIV_SXR_AM20") (pintype "power_in"))
    )
    (net (code "43") (name "Net-(U2C-VDD_MXLOBUF_RFE)") (class "Default")
      (node (ref "C53") (pin "1") (pinfunction "1_1") (pintype "passive"))
      (node (ref "U2") (pin "AN17") (pinfunction "VDD_MXLOBUF_RFE_AN17") (pintype "power_in"))
    )
    (net (code "44") (name "Net-(U2C-VDD_SPI_BUF)") (class "Default")
      (node (ref "C52") (pin "1") (pinfunction "1_1") (pintype "passive"))
      (node (ref "U2") (pin "F24") (pinfunction "VDD_SPI_BUF_F24") (pintype "power_in"))
    )
    (net (code "45") (name "Net-(U2C-VDD_TBB)") (class "Default")
      (node (ref "C51") (pin "1") (pinfunction "1_1") (pintype "passive"))
      (node (ref "U2") (pin "P4") (pinfunction "VDD_TBB_P4") (pintype "power_in"))
    )
    (net (code "46") (name "Net-(U2C-VDD_TPAD_TRF)") (class "Default")
      (node (ref "C49") (pin "1") (pinfunction "1_1") (pintype "passive"))
      (node (ref "U2") (pin "B16") (pinfunction "VDD_TPAD_TRF_B16") (pintype "power_in"))
    )
  )
)
